# Sheet1.net
KiCad netlist of a schematic drawn in Altium Designer
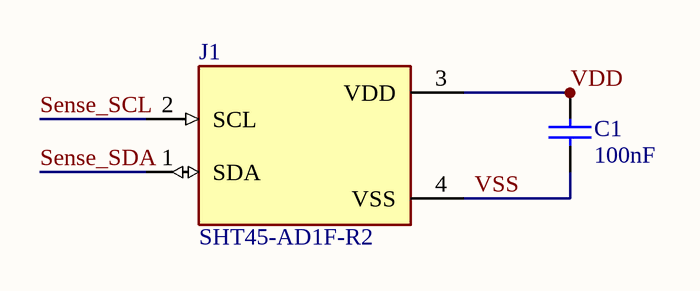
[diagram p0: Sheet1.SchDoc]

(export (version "E")
  (design (tool "Eeschema 10.0.6"))
  (components
    (comp (ref "C1")
      (value "100nF")
      (footprint "CAPC1608X90X35ML10T15")
      (description "Chip Capacitor, 10 nF, +/- 10%, 50 V, -55 to 125 degC, 0603 (1608 Metric), RoHS, Tape and Reel")
      (fields (field (name "VOLTAGE") "50V") (field (name "TOLERANCE") "10%"))
      (libsource (lib "Altium Content Vault") (part "CAP-NP-2"))
    )
    (comp (ref "J1")
      (value "SHT45-AD1F-R2")
      (footprint "SHT4X")
      (fields (field (name "MF") "Sensirion"))
      (libsource (lib "Schlib1") (part "SHT45-AD1F-R2"))
    )
  )
  (nets
    (net (code "1") (name "/Sense_SCL") (class "Default")
      (node (ref "J1") (pin "2") (pinfunction "SCL_2") (pintype "input"))
    )
    (net (code "2") (name "/Sense_SDA") (class "Default")
      (node (ref "J1") (pin "1") (pinfunction "SDA_1") (pintype "bidirectional"))
    )
    (net (code "3") (name "/VDD") (class "Default")
      (node (ref "C1") (pin "2") (pinfunction "2_2") (pintype "passive"))
      (node (ref "J1") (pin "3") (pinfunction "VDD_3") (pintype "power_in"))
    )
    (net (code "4") (name "/VSS") (class "Default")
      (node (ref "C1") (pin "1") (pinfunction "1_1") (pintype "passive"))
      (node (ref "J1") (pin "4") (pinfunction "VSS_4") (pintype "power_in"))
    )
  )
)
